# Force.net
KiCad netlist of a schematic drawn in Altium Designer
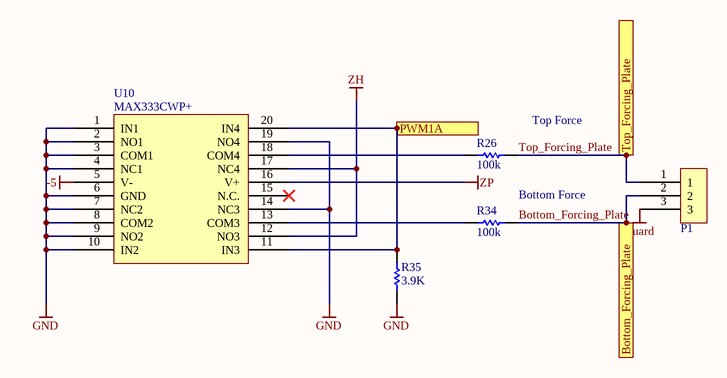
[diagram p0: Force.SchDoc]

(export (version "E")
  (design (tool "Eeschema 10.0.6"))
  (components
    (comp (ref "P1")
      (value "Triax_Conn")
      (footprint "Triax_Conn")
      (libsource (lib "ZLS_Schematic_lib") (part "Triax_Conn"))
    )
    (comp (ref "R26")
      (value "100k")
      (footprint "RESC0402(1005)_M")
      (libsource (lib "Altium Content Vault") (part "CMP-1011-00651-1"))
    )
    (comp (ref "R34")
      (value "100k")
      (footprint "RESC0402(1005)_M")
      (libsource (lib "Altium Content Vault") (part "CMP-1011-00651-1"))
    )
    (comp (ref "R35")
      (value "3.9K")
      (footprint "RESC0402(1005)_M")
      (libsource (lib "Altium Content Vault") (part "CMP-1011-00463-1"))
    )
    (comp (ref "U10")
      (value "MAX333CWP+")
      (footprint "TSOP65P640X90-20N")
      (description "IC SWITCH QUAD SPDT 20TSSOP")
      (fields (field (name "MANUFACTURER") "Maxim") (field (name "MANUFACTURER PART NUMBER") "MAX333AEUP+"))
      (libsource (lib "ZLS_Schematic_lib") (part "MAX333CWP+"))
    )
  )
  (nets
    (net (code "1") (name "-5") (class "Default")
      (node (ref "U10") (pin "5") (pinfunction "V-_5") (pintype "power_in"))
    )
    (net (code "2") (name "/Bottom_Forcing_Plate") (class "Default")
      (node (ref "P1") (pin "2") (pinfunction "2_2") (pintype "passive"))
      (node (ref "R34") (pin "1") (pinfunction "1_1") (pintype "passive"))
    )
    (net (code "3") (name "/PWM1A") (class "Default")
      (node (ref "R35") (pin "2") (pinfunction "2_2") (pintype "passive"))
      (node (ref "U10") (pin "11") (pinfunction "IN3_11") (pintype "passive"))
      (node (ref "U10") (pin "20") (pinfunction "IN4_20") (pintype "passive"))
    )
    (net (code "4") (name "/Top_Forcing_Plate") (class "Default")
      (node (ref "P1") (pin "1") (pinfunction "1_1") (pintype "passive"))
      (node (ref "R26") (pin "1") (pinfunction "1_1") (pintype "passive"))
    )
    (net (code "5") (name "GND") (class "Default")
      (node (ref "R35") (pin "1") (pinfunction "1_1") (pintype "passive"))
      (node (ref "U10") (pin "1") (pinfunction "IN1_1") (pintype "passive"))
      (node (ref "U10") (pin "10") (pinfunction "IN2_10") (pintype "passive"))
      (node (ref "U10") (pin "14") (pinfunction "NC3_14") (pintype "passive"))
      (node (ref "U10") (pin "19") (pinfunction "NO4_19") (pintype "passive"))
      (node (ref "U10") (pin "2") (pinfunction "NO1_2") (pintype "passive"))
      (node (ref "U10") (pin "3") (pinfunction "COM1_3") (pintype "passive"))
      (node (ref "U10") (pin "4") (pinfunction "NC1_4") (pintype "passive"))
      (node (ref "U10") (pin "6") (pinfunction "GND_6") (pintype "passive"))
      (node (ref "U10") (pin "7") (pinfunction "NC2_7") (pintype "passive"))
      (node (ref "U10") (pin "8") (pinfunction "COM2_8") (pintype "passive"))
      (node (ref "U10") (pin "9") (pinfunction "NO2_9") (pintype "passive"))
    )
    (net (code "6") (name "Guard") (class "Default")
      (node (ref "P1") (pin "3") (pinfunction "3_3") (pintype "passive"))
    )
    (net (code "7") (name "Net-(U10-COM3)") (class "Default")
      (node (ref "R34") (pin "2") (pinfunction "2_2") (pintype "passive"))
      (node (ref "U10") (pin "13") (pinfunction "COM3_13") (pintype "passive"))
    )
    (net (code "8") (name "Net-(U10-COM4)") (class "Default")
      (node (ref "R26") (pin "2") (pinfunction "2_2") (pintype "passive"))
      (node (ref "U10") (pin "18") (pinfunction "COM4_18") (pintype "passive"))
    )
    (net (code "9") (name "ZH") (class "Default")
      (node (ref "U10") (pin "12") (pinfunction "NO3_12") (pintype "passive"))
      (node (ref "U10") (pin "17") (pinfunction "NC4_17") (pintype "passive"))
    )
    (net (code "10") (name "ZP") (class "Default")
      (node (ref "U10") (pin "16") (pinfunction "V+_16") (pintype "power_in"))
    )
    (net (code "11") (name "unconnected-(U10-N.C.-Pad15)") (class "Default")
      (node (ref "U10") (pin "15") (pinfunction "N.C._15") (pintype "passive+no_connect"))
    )
  )
)
